# schematic_3.net
KiCad netlist of a schematic drawn in EAGLE
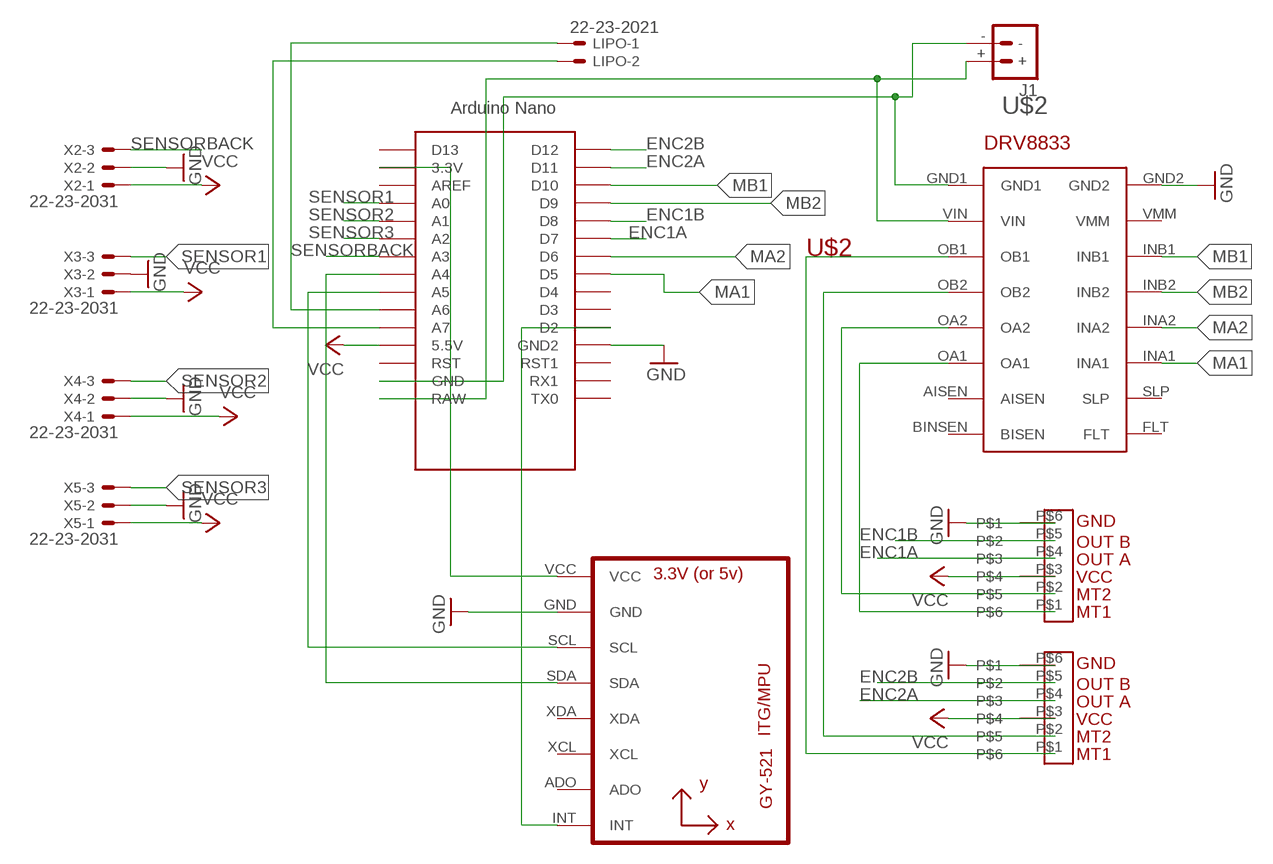
[diagram p0: schematic, sheet 1]

(export (version "E")
  (design (tool "Eeschema 10.0.6"))
  (components
    (comp (ref "J1")
      (value "BATTERY_CONN_DEANS")
      (footprint "eagle-import:DEANS")
      (libsource (lib "eagle-import") (part "BATTERY_CONN_DEANS"))
    )
    (comp (ref "LIPO")
      (value "22-23-2021")
      (footprint "eagle-import:22-23-2021")
      (fields (field (name "MF") "MOLEX"))
      (libsource (lib "eagle-import") (part "22-23-2021"))
    )
    (comp (ref "U$1")
      (value "NANO")
      (footprint "eagle-import:NANO")
      (libsource (lib "eagle-import") (part "NANO"))
    )
    (comp (ref "U$2")
      (value "POLOLU-DRV8833")
      (footprint "eagle-import:POLOLU-DRV8833")
      (libsource (lib "eagle-import") (part "POLOLU-DRV8833"))
    )
    (comp (ref "U$5")
      (value "MOTOR")
      (footprint "eagle-import:PINHEADER")
      (libsource (lib "eagle-import") (part "MOTOR"))
    )
    (comp (ref "U$6")
      (value "MOTOR")
      (footprint "eagle-import:PINHEADER")
      (libsource (lib "eagle-import") (part "MOTOR"))
    )
    (comp (ref "U1")
      (value "GY-521MPU6050")
      (footprint "eagle-import:GY-521")
      (libsource (lib "eagle-import") (part "GY-521MPU6050"))
    )
    (comp (ref "X2")
      (value "22-23-2031")
      (footprint "eagle-import:22-23-2031")
      (fields (field (name "MF") "MOLEX"))
      (libsource (lib "eagle-import") (part "22-23-2031"))
    )
    (comp (ref "X3")
      (value "22-23-2031")
      (footprint "eagle-import:22-23-2031")
      (fields (field (name "MF") "MOLEX"))
      (libsource (lib "eagle-import") (part "22-23-2031"))
    )
    (comp (ref "X4")
      (value "22-23-2031")
      (footprint "eagle-import:22-23-2031")
      (fields (field (name "MF") "MOLEX"))
      (libsource (lib "eagle-import") (part "22-23-2031"))
    )
    (comp (ref "X5")
      (value "22-23-2031")
      (footprint "eagle-import:22-23-2031")
      (fields (field (name "MF") "MOLEX"))
      (libsource (lib "eagle-import") (part "22-23-2031"))
    )
  )
  (nets
    (net (code "1") (name "/ENC1A") (class "Default")
      (node (ref "U$1") (pin "D7") (pinfunction "D7_D7") (pintype "bidirectional"))
      (node (ref "U$5") (pin "P$4") (pinfunction "P$3_P$4") (pintype "bidirectional"))
    )
    (net (code "2") (name "/ENC1B") (class "Default")
      (node (ref "U$1") (pin "D8") (pinfunction "D8_D8") (pintype "bidirectional"))
      (node (ref "U$5") (pin "P$5") (pinfunction "P$2_P$5") (pintype "bidirectional"))
    )
    (net (code "3") (name "/ENC2A") (class "Default")
      (node (ref "U$1") (pin "D11") (pinfunction "D11_D11") (pintype "bidirectional"))
      (node (ref "U$6") (pin "P$4") (pinfunction "P$3_P$4") (pintype "bidirectional"))
    )
    (net (code "4") (name "/ENC2B") (class "Default")
      (node (ref "U$1") (pin "D12") (pinfunction "D12_D12") (pintype "bidirectional"))
      (node (ref "U$6") (pin "P$5") (pinfunction "P$2_P$5") (pintype "bidirectional"))
    )
    (net (code "5") (name "/SENSORBACK") (class "Default")
      (node (ref "U$1") (pin "A3") (pinfunction "A3_A3") (pintype "bidirectional"))
      (node (ref "X2") (pin "3") (pinfunction "S_3") (pintype "passive"))
    )
    (net (code "6") (name "GND") (class "Default")
      (node (ref "U$1") (pin "GND1") (pinfunction "GND2_GND1") (pintype "bidirectional"))
      (node (ref "U$2") (pin "GND2") (pinfunction "GND2_GND2") (pintype "bidirectional"))
      (node (ref "U$5") (pin "P$6") (pinfunction "P$1_P$6") (pintype "bidirectional"))
      (node (ref "U$6") (pin "P$6") (pinfunction "P$1_P$6") (pintype "bidirectional"))
      (node (ref "U1") (pin "GND") (pinfunction "GND_GND") (pintype "bidirectional"))
      (node (ref "X2") (pin "2") (pinfunction "S_2") (pintype "passive"))
      (node (ref "X3") (pin "2") (pinfunction "S_2") (pintype "passive"))
      (node (ref "X4") (pin "2") (pinfunction "S_2") (pintype "passive"))
      (node (ref "X5") (pin "2") (pinfunction "S_2") (pintype "passive"))
    )
    (net (code "7") (name "MA1") (class "Default")
      (node (ref "U$1") (pin "D5") (pinfunction "D5_D5") (pintype "bidirectional"))
      (node (ref "U$2") (pin "INA1") (pinfunction "INA1_INA1") (pintype "bidirectional"))
    )
    (net (code "8") (name "MA2") (class "Default")
      (node (ref "U$1") (pin "D6") (pinfunction "D6_D6") (pintype "bidirectional"))
      (node (ref "U$2") (pin "INA2") (pinfunction "INA2_INA2") (pintype "bidirectional"))
    )
    (net (code "9") (name "MB1") (class "Default")
      (node (ref "U$1") (pin "D10") (pinfunction "D10_D10") (pintype "bidirectional"))
      (node (ref "U$2") (pin "INB1") (pinfunction "INB1_INB1") (pintype "bidirectional"))
    )
    (net (code "10") (name "MB2") (class "Default")
      (node (ref "U$1") (pin "D9") (pinfunction "D9_D9") (pintype "bidirectional"))
      (node (ref "U$2") (pin "INB2") (pinfunction "INB2_INB2") (pintype "bidirectional"))
    )
    (net (code "11") (name "Net-(J1-Pad+)") (class "Default")
      (node (ref "J1") (pin "+") (pinfunction "+_+") (pintype "passive"))
      (node (ref "U$1") (pin "RAW") (pinfunction "RAW_RAW") (pintype "bidirectional"))
      (node (ref "U$2") (pin "VIN") (pinfunction "VIN_VIN") (pintype "bidirectional"))
    )
    (net (code "12") (name "Net-(J1-Pad-)") (class "Default")
      (node (ref "J1") (pin "-") (pinfunction "-_-") (pintype "passive"))
      (node (ref "U$1") (pin "GND") (pinfunction "GND_GND") (pintype "bidirectional"))
      (node (ref "U$2") (pin "GND1") (pinfunction "GND1_GND1") (pintype "bidirectional"))
    )
    (net (code "13") (name "Net-(LIPOA-S)") (class "Default")
      (node (ref "LIPO") (pin "1") (pinfunction "S_1") (pintype "passive"))
      (node (ref "U$1") (pin "A6") (pinfunction "A6_A6") (pintype "bidirectional"))
    )
    (net (code "14") (name "Net-(LIPOB-S)") (class "Default")
      (node (ref "LIPO") (pin "2") (pinfunction "S_2") (pintype "passive"))
      (node (ref "U$1") (pin "A7") (pinfunction "A7_A7") (pintype "bidirectional"))
    )
    (net (code "15") (name "Net-(U$1-Pad3.3V)") (class "Default")
      (node (ref "U$1") (pin "3.3V") (pinfunction "3.3V_3.3V") (pintype "bidirectional"))
      (node (ref "U1") (pin "VCC") (pinfunction "VCC_VCC") (pintype "bidirectional"))
    )
    (net (code "16") (name "Net-(U$1-PadA4)") (class "Default")
      (node (ref "U$1") (pin "A4") (pinfunction "A4_A4") (pintype "bidirectional"))
      (node (ref "U1") (pin "SDA") (pinfunction "SDA_SDA") (pintype "bidirectional"))
    )
    (net (code "17") (name "Net-(U$1-PadA5)") (class "Default")
      (node (ref "U$1") (pin "A5") (pinfunction "A5_A5") (pintype "bidirectional"))
      (node (ref "U1") (pin "SCL") (pinfunction "SCL_SCL") (pintype "bidirectional"))
    )
    (net (code "18") (name "Net-(U$1-PadD2)") (class "Default")
      (node (ref "U$1") (pin "D2") (pinfunction "D2_D2") (pintype "bidirectional"))
      (node (ref "U1") (pin "INT") (pinfunction "INT_INT") (pintype "bidirectional"))
    )
    (net (code "19") (name "Net-(U$5-P$5)") (class "Default")
      (node (ref "U$2") (pin "OA2") (pinfunction "OA2_OA2") (pintype "bidirectional"))
      (node (ref "U$5") (pin "P$2") (pinfunction "P$5_P$2") (pintype "bidirectional"))
    )
    (net (code "20") (name "Net-(U$5-P$6)") (class "Default")
      (node (ref "U$2") (pin "OA1") (pinfunction "OA1_OA1") (pintype "bidirectional"))
      (node (ref "U$5") (pin "P$1") (pinfunction "P$6_P$1") (pintype "bidirectional"))
    )
    (net (code "21") (name "Net-(U$6-P$5)") (class "Default")
      (node (ref "U$2") (pin "OB2") (pinfunction "OB2_OB2") (pintype "bidirectional"))
      (node (ref "U$6") (pin "P$2") (pinfunction "P$5_P$2") (pintype "bidirectional"))
    )
    (net (code "22") (name "Net-(U$6-P$6)") (class "Default")
      (node (ref "U$2") (pin "OB1") (pinfunction "OB1_OB1") (pintype "bidirectional"))
      (node (ref "U$6") (pin "P$1") (pinfunction "P$6_P$1") (pintype "bidirectional"))
    )
    (net (code "23") (name "SENSOR1") (class "Default")
      (node (ref "U$1") (pin "A0") (pinfunction "A0_A0") (pintype "bidirectional"))
      (node (ref "X3") (pin "3") (pinfunction "S_3") (pintype "passive"))
    )
    (net (code "24") (name "SENSOR2") (class "Default")
      (node (ref "U$1") (pin "A1") (pinfunction "A1_A1") (pintype "bidirectional"))
      (node (ref "X4") (pin "3") (pinfunction "S_3") (pintype "passive"))
    )
    (net (code "25") (name "SENSOR3") (class "Default")
      (node (ref "U$1") (pin "A2") (pinfunction "A2_A2") (pintype "bidirectional"))
      (node (ref "X5") (pin "3") (pinfunction "S_3") (pintype "passive"))
    )
    (net (code "26") (name "VCC") (class "Default")
      (node (ref "U$1") (pin "5V") (pinfunction "5.5V_5V") (pintype "bidirectional"))
      (node (ref "U$5") (pin "P$3") (pinfunction "P$4_P$3") (pintype "bidirectional"))
      (node (ref "U$6") (pin "P$3") (pinfunction "P$4_P$3") (pintype "bidirectional"))
      (node (ref "X2") (pin "1") (pinfunction "S_1") (pintype "passive"))
      (node (ref "X3") (pin "1") (pinfunction "S_1") (pintype "passive"))
      (node (ref "X4") (pin "1") (pinfunction "S_1") (pintype "passive"))
      (node (ref "X5") (pin "1") (pinfunction "S_1") (pintype "passive"))
    )
    (net (code "27") (name "unconnected-(U$1-PadAREF)") (class "Default")
      (node (ref "U$1") (pin "AREF") (pinfunction "AREF_AREF") (pintype "bidirectional"))
    )
    (net (code "28") (name "unconnected-(U$1-PadD3)") (class "Default")
      (node (ref "U$1") (pin "D3") (pinfunction "D3_D3") (pintype "bidirectional"))
    )
    (net (code "29") (name "unconnected-(U$1-PadD4)") (class "Default")
      (node (ref "U$1") (pin "D4") (pinfunction "D4_D4") (pintype "bidirectional"))
    )
    (net (code "30") (name "unconnected-(U$1-PadD13)") (class "Default")
      (node (ref "U$1") (pin "D13") (pinfunction "D13_D13") (pintype "bidirectional"))
    )
    (net (code "31") (name "unconnected-(U$1-PadICSP1)") (class "Default")
      (node (ref "U$1") (pin "ICSP1") (pinfunction "ICSP1_ICSP1") (pintype "bidirectional"))
    )
    (net (code "32") (name "unconnected-(U$1-PadICSP2)") (class "Default")
      (node (ref "U$1") (pin "ICSP2") (pinfunction "ICSP2_ICSP2") (pintype "bidirectional"))
    )
    (net (code "33") (name "unconnected-(U$1-PadICSP3)") (class "Default")
      (node (ref "U$1") (pin "ICSP3") (pinfunction "ICSP3_ICSP3") (pintype "bidirectional"))
    )
    (net (code "34") (name "unconnected-(U$1-PadICSP4)") (class "Default")
      (node (ref "U$1") (pin "ICSP4") (pinfunction "ICSP4_ICSP4") (pintype "bidirectional"))
    )
    (net (code "35") (name "unconnected-(U$1-PadICSP5)") (class "Default")
      (node (ref "U$1") (pin "ICSP5") (pinfunction "ICSP5_ICSP5") (pintype "bidirectional"))
    )
    (net (code "36") (name "unconnected-(U$1-PadICSP6)") (class "Default")
      (node (ref "U$1") (pin "ICSP6") (pinfunction "ICSP6_ICSP6") (pintype "bidirectional"))
    )
    (net (code "37") (name "unconnected-(U$1-PadRST)") (class "Default")
      (node (ref "U$1") (pin "RST") (pinfunction "RST_RST") (pintype "bidirectional"))
    )
    (net (code "38") (name "unconnected-(U$1-PadRST1)") (class "Default")
      (node (ref "U$1") (pin "RST1") (pinfunction "RST1_RST1") (pintype "bidirectional"))
    )
    (net (code "39") (name "unconnected-(U$1-PadRX1)") (class "Default")
      (node (ref "U$1") (pin "RX1") (pinfunction "RX1_RX1") (pintype "bidirectional"))
    )
    (net (code "40") (name "unconnected-(U$1-PadTX0)") (class "Default")
      (node (ref "U$1") (pin "TX0") (pinfunction "TX0_TX0") (pintype "bidirectional"))
    )
    (net (code "41") (name "unconnected-(U$2-BISEN-PadBINSEN)") (class "Default")
      (node (ref "U$2") (pin "BINSEN") (pinfunction "BISEN_BINSEN") (pintype "bidirectional"))
    )
    (net (code "42") (name "unconnected-(U$2-PadAISEN)") (class "Default")
      (node (ref "U$2") (pin "AISEN") (pinfunction "AISEN_AISEN") (pintype "bidirectional"))
    )
    (net (code "43") (name "unconnected-(U$2-PadFLT)") (class "Default")
      (node (ref "U$2") (pin "FLT") (pinfunction "FLT_FLT") (pintype "bidirectional"))
    )
    (net (code "44") (name "unconnected-(U$2-PadSLP)") (class "Default")
      (node (ref "U$2") (pin "SLP") (pinfunction "SLP_SLP") (pintype "bidirectional"))
    )
    (net (code "45") (name "unconnected-(U$2-PadVMM)") (class "Default")
      (node (ref "U$2") (pin "VMM") (pinfunction "VMM_VMM") (pintype "output"))
    )
    (net (code "46") (name "unconnected-(U1-PadADO)") (class "Default")
      (node (ref "U1") (pin "ADO") (pinfunction "ADO_ADO") (pintype "bidirectional"))
    )
    (net (code "47") (name "unconnected-(U1-PadXCL)") (class "Default")
      (node (ref "U1") (pin "XCL") (pinfunction "XCL_XCL") (pintype "bidirectional"))
    )
    (net (code "48") (name "unconnected-(U1-PadXDA)") (class "Default")
      (node (ref "U1") (pin "XDA") (pinfunction "XDA_XDA") (pintype "bidirectional"))
    )
  )
)
